# geiger.net
KiCad netlist of a schematic drawn in EAGLE
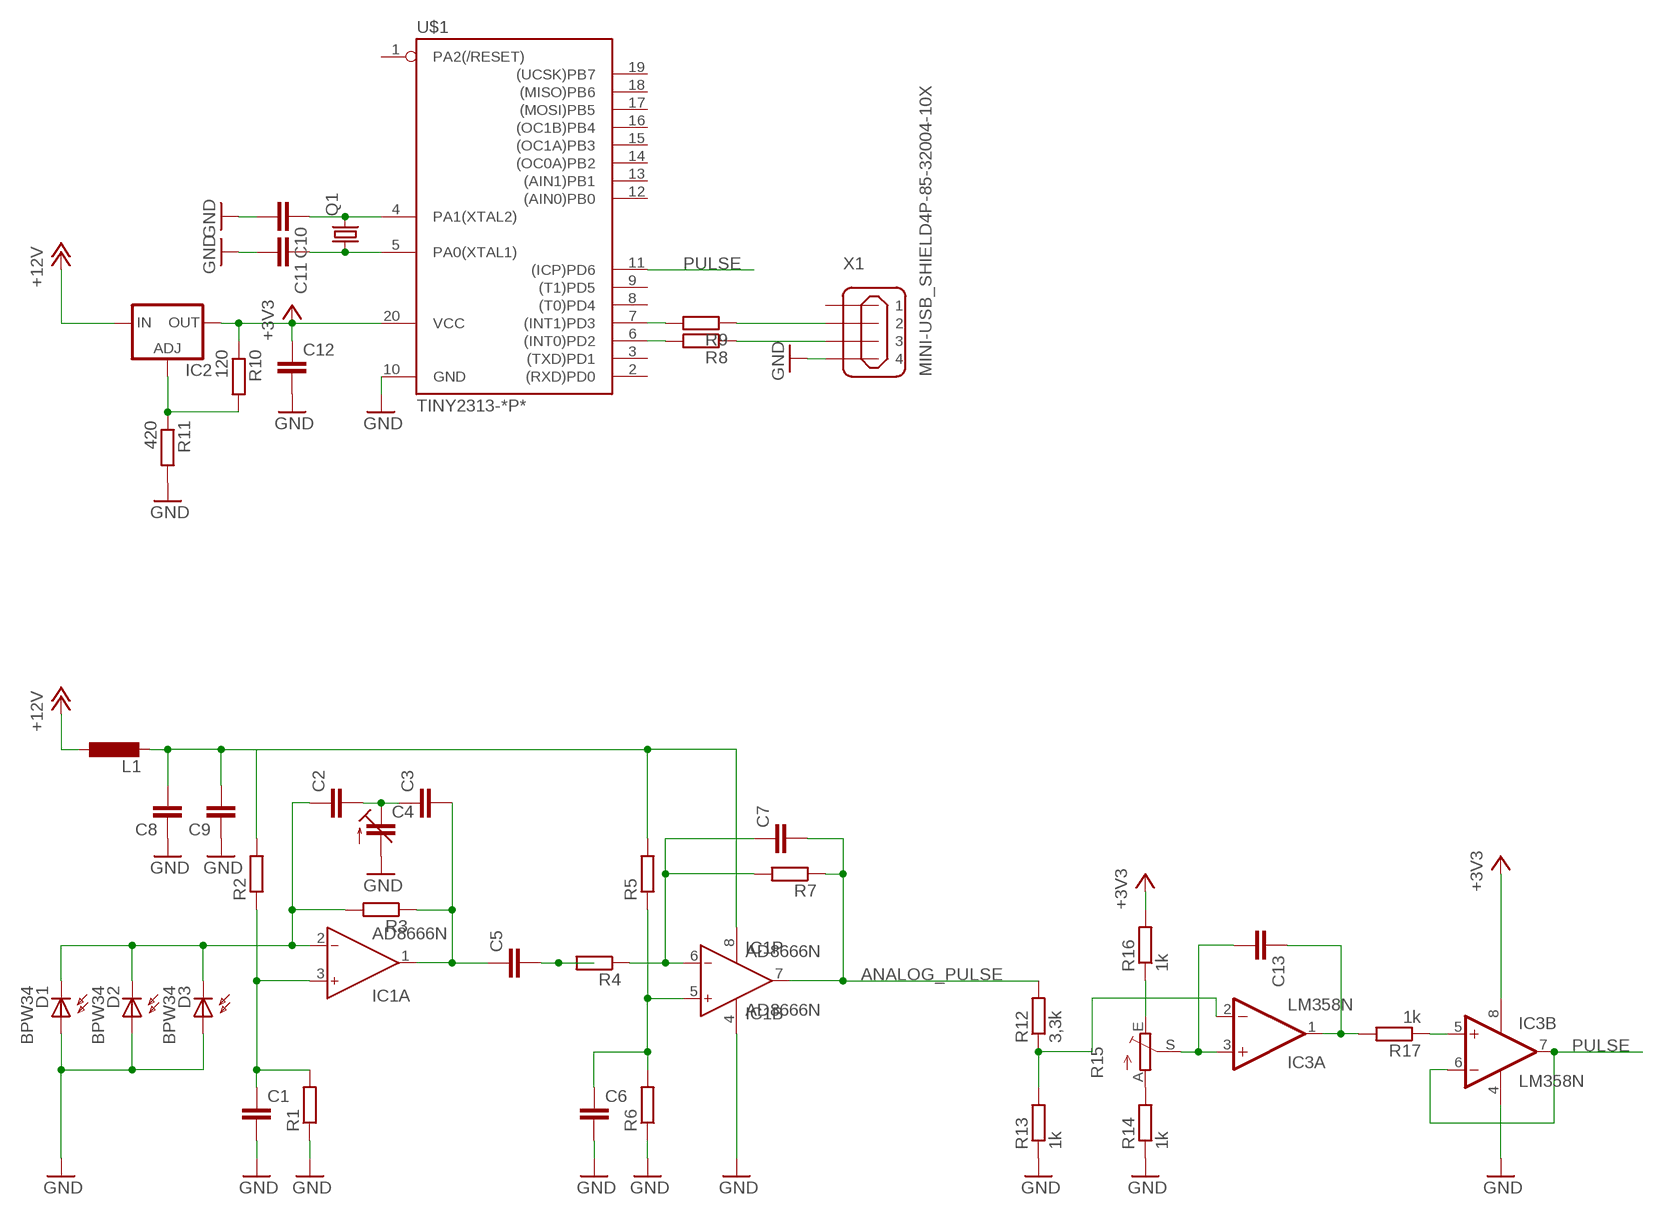
[diagram p0: schematic, sheet 1]

(export (version "E")
  (design (tool "Eeschema 10.0.6"))
  (components
    (comp (ref "C1")
      (value "C-EU025-025X050")
      (footprint "eagle-import:C025-025X050")
      (libsource (lib "eagle-import") (part "C-EU025-025X050"))
    )
    (comp (ref "C2")
      (value "C-EU025-025X050")
      (footprint "eagle-import:C025-025X050")
      (libsource (lib "eagle-import") (part "C-EU025-025X050"))
    )
    (comp (ref "C3")
      (value "C-EU025-025X050")
      (footprint "eagle-import:C025-025X050")
      (libsource (lib "eagle-import") (part "C-EU025-025X050"))
    )
    (comp (ref "C4")
      (value "C-TRIMM3050.504")
      (footprint "eagle-import:CTRIM3050.504")
      (libsource (lib "eagle-import") (part "C-TRIMM3050.504"))
    )
    (comp (ref "C5")
      (value "C-EU025-025X050")
      (footprint "eagle-import:C025-025X050")
      (libsource (lib "eagle-import") (part "C-EU025-025X050"))
    )
    (comp (ref "C6")
      (value "C-EU025-025X050")
      (footprint "eagle-import:C025-025X050")
      (libsource (lib "eagle-import") (part "C-EU025-025X050"))
    )
    (comp (ref "C7")
      (value "C-EU025-025X050")
      (footprint "eagle-import:C025-025X050")
      (libsource (lib "eagle-import") (part "C-EU025-025X050"))
    )
    (comp (ref "C8")
      (value "C-EU025-025X050")
      (footprint "eagle-import:C025-025X050")
      (libsource (lib "eagle-import") (part "C-EU025-025X050"))
    )
    (comp (ref "C9")
      (value "C-EU025-025X050")
      (footprint "eagle-import:C025-025X050")
      (libsource (lib "eagle-import") (part "C-EU025-025X050"))
    )
    (comp (ref "C10")
      (value "C-EU025-025X050")
      (footprint "eagle-import:C025-025X050")
      (libsource (lib "eagle-import") (part "C-EU025-025X050"))
    )
    (comp (ref "C11")
      (value "C-EU025-025X050")
      (footprint "eagle-import:C025-025X050")
      (libsource (lib "eagle-import") (part "C-EU025-025X050"))
    )
    (comp (ref "C12")
      (value "C-EU025-025X050")
      (footprint "eagle-import:C025-025X050")
      (libsource (lib "eagle-import") (part "C-EU025-025X050"))
    )
    (comp (ref "C13")
      (value "C-EU025-025X050")
      (footprint "eagle-import:C025-025X050")
      (libsource (lib "eagle-import") (part "C-EU025-025X050"))
    )
    (comp (ref "D1")
      (value "BPW34")
      (footprint "eagle-import:BPW32")
      (libsource (lib "eagle-import") (part "BPW32"))
    )
    (comp (ref "D2")
      (value "BPW34")
      (footprint "eagle-import:BPW32")
      (libsource (lib "eagle-import") (part "BPW32"))
    )
    (comp (ref "D3")
      (value "BPW34")
      (footprint "eagle-import:BPW32")
      (libsource (lib "eagle-import") (part "BPW32"))
    )
    (comp (ref "IC1")
      (value "AD8666N")
      (footprint "eagle-import:DIL08")
      (libsource (lib "eagle-import") (part "AD8066N"))
    )
    (comp (ref "IC2")
      (value "LM317L")
      (footprint "eagle-import:317L")
      (libsource (lib "eagle-import") (part "LM317L"))
    )
    (comp (ref "IC3")
      (value "LM358N")
      (footprint "eagle-import:DIL08")
      (libsource (lib "eagle-import") (part "LM358N"))
    )
    (comp (ref "L1")
      (value "L-EU2200-12.7")
      (footprint "eagle-import:2200-12.7")
      (libsource (lib "eagle-import") (part "L-EU2200-12.7"))
    )
    (comp (ref "Q1")
      (value "CRYSTALHC49S")
      (footprint "eagle-import:HC49_S")
      (libsource (lib "eagle-import") (part "CRYSTALHC49S"))
    )
    (comp (ref "R1")
      (value "R-EU_0207/7")
      (footprint "eagle-import:0207_7")
      (libsource (lib "eagle-import") (part "R-EU_0207/7"))
    )
    (comp (ref "R2")
      (value "R-EU_0207/7")
      (footprint "eagle-import:0207_7")
      (libsource (lib "eagle-import") (part "R-EU_0207/7"))
    )
    (comp (ref "R3")
      (value "R-EU_0207/7")
      (footprint "eagle-import:0207_7")
      (libsource (lib "eagle-import") (part "R-EU_0207/7"))
    )
    (comp (ref "R4")
      (value "R-EU_0207/7")
      (footprint "eagle-import:0207_7")
      (libsource (lib "eagle-import") (part "R-EU_0207/7"))
    )
    (comp (ref "R5")
      (value "R-EU_0207/7")
      (footprint "eagle-import:0207_7")
      (libsource (lib "eagle-import") (part "R-EU_0207/7"))
    )
    (comp (ref "R6")
      (value "R-EU_0207/7")
      (footprint "eagle-import:0207_7")
      (libsource (lib "eagle-import") (part "R-EU_0207/7"))
    )
    (comp (ref "R7")
      (value "R-EU_0207/7")
      (footprint "eagle-import:0207_7")
      (libsource (lib "eagle-import") (part "R-EU_0207/7"))
    )
    (comp (ref "R8")
      (value "R-EU_0207/7")
      (footprint "eagle-import:0207_7")
      (libsource (lib "eagle-import") (part "R-EU_0207/7"))
    )
    (comp (ref "R9")
      (value "R-EU_0207/7")
      (footprint "eagle-import:0207_7")
      (libsource (lib "eagle-import") (part "R-EU_0207/7"))
    )
    (comp (ref "R10")
      (value "120")
      (footprint "eagle-import:0207_7")
      (libsource (lib "eagle-import") (part "R-EU_0207/7"))
    )
    (comp (ref "R11")
      (value "420")
      (footprint "eagle-import:0207_7")
      (libsource (lib "eagle-import") (part "R-EU_0207/7"))
    )
    (comp (ref "R12")
      (value "3,3k")
      (footprint "eagle-import:0207_7")
      (libsource (lib "eagle-import") (part "R-EU_0207/7"))
    )
    (comp (ref "R13")
      (value "1k")
      (footprint "eagle-import:0207_7")
      (libsource (lib "eagle-import") (part "R-EU_0207/7"))
    )
    (comp (ref "R14")
      (value "1k")
      (footprint "eagle-import:0207_7")
      (libsource (lib "eagle-import") (part "R-EU_0207/7"))
    )
    (comp (ref "R15")
      (value "TRIM_EU-LI10")
      (footprint "eagle-import:LI10")
      (libsource (lib "eagle-import") (part "TRIM_EU-LI10"))
    )
    (comp (ref "R16")
      (value "1k")
      (footprint "eagle-import:0207_7")
      (libsource (lib "eagle-import") (part "R-EU_0207/7"))
    )
    (comp (ref "R17")
      (value "1k")
      (footprint "eagle-import:0207_7")
      (libsource (lib "eagle-import") (part "R-EU_0207/7"))
    )
    (comp (ref "U$1")
      (value "TINY2313-*P*")
      (footprint "eagle-import:DIL20")
      (libsource (lib "eagle-import") (part "TINY2313-P"))
    )
    (comp (ref "X1")
      (value "MINI-USB_SHIELD4P-85-32004-10X")
      (footprint "eagle-import:85-32004-10X")
      (libsource (lib "eagle-import") (part "MINI-USB_SHIELD4P-85-32004-10X"))
    )
  )
  (nets
    (net (code "1") (name "+3V3") (class "Default")
      (node (ref "C12") (pin "1") (pinfunction "1_1") (pintype "passive"))
      (node (ref "IC2") (pin "2") (pinfunction "OUT_2") (pintype "passive"))
      (node (ref "IC3") (pin "8") (pinfunction "V+_8") (pintype "power_in"))
      (node (ref "R10") (pin "1") (pinfunction "1_1") (pintype "passive"))
      (node (ref "R16") (pin "2") (pinfunction "2_2") (pintype "passive"))
      (node (ref "U$1") (pin "20") (pinfunction "VCC_20") (pintype "power_in"))
    )
    (net (code "2") (name "+12V") (class "Default")
      (node (ref "IC2") (pin "3") (pinfunction "IN_3") (pintype "input"))
      (node (ref "L1") (pin "1") (pinfunction "1_1") (pintype "passive"))
    )
    (net (code "3") (name "/ANALOG_PULSE") (class "Default")
      (node (ref "C7") (pin "2") (pinfunction "2_2") (pintype "passive"))
      (node (ref "IC1") (pin "7") (pinfunction "OUT_7") (pintype "output"))
      (node (ref "R12") (pin "2") (pinfunction "2_2") (pintype "passive"))
      (node (ref "R7") (pin "1") (pinfunction "1_1") (pintype "passive"))
    )
    (net (code "4") (name "/PULSE") (class "Default")
      (node (ref "IC3") (pin "6") (pinfunction "-IN_6") (pintype "input"))
      (node (ref "IC3") (pin "7") (pinfunction "OUT_7") (pintype "output"))
      (node (ref "U$1") (pin "11") (pinfunction "(ICP)PD6_11") (pintype "bidirectional"))
    )
    (net (code "5") (name "GND") (class "Default")
      (node (ref "C1") (pin "2") (pinfunction "2_2") (pintype "passive"))
      (node (ref "C10") (pin "2") (pinfunction "2_2") (pintype "passive"))
      (node (ref "C11") (pin "2") (pinfunction "2_2") (pintype "passive"))
      (node (ref "C12") (pin "2") (pinfunction "2_2") (pintype "passive"))
      (node (ref "C4") (pin "2") (pinfunction "A_2") (pintype "passive"))
      (node (ref "C6") (pin "2") (pinfunction "2_2") (pintype "passive"))
      (node (ref "C8") (pin "1") (pinfunction "1_1") (pintype "passive"))
      (node (ref "C9") (pin "1") (pinfunction "1_1") (pintype "passive"))
      (node (ref "D1") (pin "A") (pinfunction "A_A") (pintype "passive"))
      (node (ref "D2") (pin "A") (pinfunction "A_A") (pintype "passive"))
      (node (ref "D3") (pin "A") (pinfunction "A_A") (pintype "passive"))
      (node (ref "IC1") (pin "4") (pinfunction "V-_4") (pintype "power_in"))
      (node (ref "IC3") (pin "4") (pinfunction "V-_4") (pintype "power_in"))
      (node (ref "R1") (pin "1") (pinfunction "1_1") (pintype "passive"))
      (node (ref "R11") (pin "2") (pinfunction "2_2") (pintype "passive"))
      (node (ref "R13") (pin "1") (pinfunction "1_1") (pintype "passive"))
      (node (ref "R14") (pin "1") (pinfunction "1_1") (pintype "passive"))
      (node (ref "R6") (pin "1") (pinfunction "1_1") (pintype "passive"))
      (node (ref "U$1") (pin "10") (pinfunction "GND_10") (pintype "power_in"))
      (node (ref "X1") (pin "4") (pinfunction "4_4") (pintype "passive"))
    )
    (net (code "6") (name "Net-(C4-E)") (class "Default")
      (node (ref "C2") (pin "2") (pinfunction "2_2") (pintype "passive"))
      (node (ref "C3") (pin "1") (pinfunction "1_1") (pintype "passive"))
      (node (ref "C4") (pin "1") (pinfunction "E_1") (pintype "passive"))
    )
    (net (code "7") (name "Net-(C5-Pad2)") (class "Default")
      (node (ref "C5") (pin "2") (pinfunction "2_2") (pintype "passive"))
      (node (ref "R4") (pin "2") (pinfunction "2_2") (pintype "passive"))
    )
    (net (code "8") (name "Net-(D1-C)") (class "Default")
      (node (ref "C2") (pin "1") (pinfunction "1_1") (pintype "passive"))
      (node (ref "D1") (pin "K") (pinfunction "C_K") (pintype "passive"))
      (node (ref "D2") (pin "K") (pinfunction "C_K") (pintype "passive"))
      (node (ref "D3") (pin "K") (pinfunction "C_K") (pintype "passive"))
      (node (ref "IC1") (pin "2") (pinfunction "IN-_2") (pintype "input"))
      (node (ref "R3") (pin "2") (pinfunction "2_2") (pintype "passive"))
    )
    (net (code "9") (name "Net-(IC1A-IN+)") (class "Default")
      (node (ref "C1") (pin "1") (pinfunction "1_1") (pintype "passive"))
      (node (ref "IC1") (pin "3") (pinfunction "IN+_3") (pintype "input"))
      (node (ref "R1") (pin "2") (pinfunction "2_2") (pintype "passive"))
      (node (ref "R2") (pin "1") (pinfunction "1_1") (pintype "passive"))
    )
    (net (code "10") (name "Net-(IC1A-OUT)") (class "Default")
      (node (ref "C3") (pin "2") (pinfunction "2_2") (pintype "passive"))
      (node (ref "C5") (pin "1") (pinfunction "1_1") (pintype "passive"))
      (node (ref "IC1") (pin "1") (pinfunction "OUT_1") (pintype "output"))
      (node (ref "R3") (pin "1") (pinfunction "1_1") (pintype "passive"))
    )
    (net (code "11") (name "Net-(IC1B-IN+)") (class "Default")
      (node (ref "C6") (pin "1") (pinfunction "1_1") (pintype "passive"))
      (node (ref "IC1") (pin "5") (pinfunction "IN+_5") (pintype "input"))
      (node (ref "R5") (pin "1") (pinfunction "1_1") (pintype "passive"))
      (node (ref "R6") (pin "2") (pinfunction "2_2") (pintype "passive"))
    )
    (net (code "12") (name "Net-(IC1B-IN-)") (class "Default")
      (node (ref "C7") (pin "1") (pinfunction "1_1") (pintype "passive"))
      (node (ref "IC1") (pin "6") (pinfunction "IN-_6") (pintype "input"))
      (node (ref "R4") (pin "1") (pinfunction "1_1") (pintype "passive"))
      (node (ref "R7") (pin "2") (pinfunction "2_2") (pintype "passive"))
    )
    (net (code "13") (name "Net-(IC1C-V+)") (class "Default")
      (node (ref "C8") (pin "2") (pinfunction "2_2") (pintype "passive"))
      (node (ref "C9") (pin "2") (pinfunction "2_2") (pintype "passive"))
      (node (ref "IC1") (pin "8") (pinfunction "V+_8") (pintype "power_in"))
      (node (ref "L1") (pin "2") (pinfunction "2_2") (pintype "passive"))
      (node (ref "R2") (pin "2") (pinfunction "2_2") (pintype "passive"))
      (node (ref "R5") (pin "2") (pinfunction "2_2") (pintype "passive"))
    )
    (net (code "14") (name "Net-(IC2-ADJ)") (class "Default")
      (node (ref "IC2") (pin "1") (pinfunction "ADJ_1") (pintype "input"))
      (node (ref "R10") (pin "2") (pinfunction "2_2") (pintype "passive"))
      (node (ref "R11") (pin "1") (pinfunction "1_1") (pintype "passive"))
    )
    (net (code "15") (name "Net-(IC3A-+IN)") (class "Default")
      (node (ref "C13") (pin "2") (pinfunction "2_2") (pintype "passive"))
      (node (ref "IC3") (pin "3") (pinfunction "+IN_3") (pintype "input"))
      (node (ref "R15") (pin "S") (pinfunction "S_S") (pintype "passive"))
    )
    (net (code "16") (name "Net-(IC3A--IN)") (class "Default")
      (node (ref "IC3") (pin "2") (pinfunction "-IN_2") (pintype "input"))
      (node (ref "R12") (pin "1") (pinfunction "1_1") (pintype "passive"))
      (node (ref "R13") (pin "2") (pinfunction "2_2") (pintype "passive"))
    )
    (net (code "17") (name "Net-(IC3A-OUT)") (class "Default")
      (node (ref "C13") (pin "1") (pinfunction "1_1") (pintype "passive"))
      (node (ref "IC3") (pin "1") (pinfunction "OUT_1") (pintype "output"))
      (node (ref "R17") (pin "2") (pinfunction "2_2") (pintype "passive"))
    )
    (net (code "18") (name "Net-(IC3B-+IN)") (class "Default")
      (node (ref "IC3") (pin "5") (pinfunction "+IN_5") (pintype "input"))
      (node (ref "R17") (pin "1") (pinfunction "1_1") (pintype "passive"))
    )
    (net (code "19") (name "Net-(R8-Pad1)") (class "Default")
      (node (ref "R8") (pin "1") (pinfunction "1_1") (pintype "passive"))
      (node (ref "X1") (pin "3") (pinfunction "3_3") (pintype "passive"))
    )
    (net (code "20") (name "Net-(R9-Pad1)") (class "Default")
      (node (ref "R9") (pin "1") (pinfunction "1_1") (pintype "passive"))
      (node (ref "X1") (pin "2") (pinfunction "2_2") (pintype "passive"))
    )
    (net (code "21") (name "Net-(R14-Pad2)") (class "Default")
      (node (ref "R14") (pin "2") (pinfunction "2_2") (pintype "passive"))
      (node (ref "R15") (pin "A") (pinfunction "A_A") (pintype "passive"))
    )
    (net (code "22") (name "Net-(R15-PadE)") (class "Default")
      (node (ref "R15") (pin "E") (pinfunction "E_E") (pintype "passive"))
      (node (ref "R16") (pin "1") (pinfunction "1_1") (pintype "passive"))
    )
    (net (code "23") (name "Net-(U$1-(INT0)PD2)") (class "Default")
      (node (ref "R8") (pin "2") (pinfunction "2_2") (pintype "passive"))
      (node (ref "U$1") (pin "6") (pinfunction "(INT0)PD2_6") (pintype "bidirectional"))
    )
    (net (code "24") (name "Net-(U$1-(INT1)PD3)") (class "Default")
      (node (ref "R9") (pin "2") (pinfunction "2_2") (pintype "passive"))
      (node (ref "U$1") (pin "7") (pinfunction "(INT1)PD3_7") (pintype "bidirectional"))
    )
    (net (code "25") (name "Net-(U$1-PA0(XTAL1))") (class "Default")
      (node (ref "C11") (pin "1") (pinfunction "1_1") (pintype "passive"))
      (node (ref "Q1") (pin "1") (pinfunction "1_1") (pintype "passive"))
      (node (ref "U$1") (pin "5") (pinfunction "PA0(XTAL1)_5") (pintype "bidirectional"))
    )
    (net (code "26") (name "Net-(U$1-PA1(XTAL2))") (class "Default")
      (node (ref "C10") (pin "1") (pinfunction "1_1") (pintype "passive"))
      (node (ref "Q1") (pin "2") (pinfunction "2_2") (pintype "passive"))
      (node (ref "U$1") (pin "4") (pinfunction "PA1(XTAL2)_4") (pintype "bidirectional"))
    )
    (net (code "27") (name "unconnected-(U$1-(AIN0)PB0-Pad12)") (class "Default")
      (node (ref "U$1") (pin "12") (pinfunction "(AIN0)PB0_12") (pintype "bidirectional"))
    )
    (net (code "28") (name "unconnected-(U$1-(AIN1)PB1-Pad13)") (class "Default")
      (node (ref "U$1") (pin "13") (pinfunction "(AIN1)PB1_13") (pintype "bidirectional"))
    )
    (net (code "29") (name "unconnected-(U$1-(MISO)PB6-Pad18)") (class "Default")
      (node (ref "U$1") (pin "18") (pinfunction "(MISO)PB6_18") (pintype "bidirectional"))
    )
    (net (code "30") (name "unconnected-(U$1-(MOSI)PB5-Pad17)") (class "Default")
      (node (ref "U$1") (pin "17") (pinfunction "(MOSI)PB5_17") (pintype "bidirectional"))
    )
    (net (code "31") (name "unconnected-(U$1-(OC0A)PB2-Pad14)") (class "Default")
      (node (ref "U$1") (pin "14") (pinfunction "(OC0A)PB2_14") (pintype "bidirectional"))
    )
    (net (code "32") (name "unconnected-(U$1-(OC1A)PB3-Pad15)") (class "Default")
      (node (ref "U$1") (pin "15") (pinfunction "(OC1A)PB3_15") (pintype "bidirectional"))
    )
    (net (code "33") (name "unconnected-(U$1-(OC1B)PB4-Pad16)") (class "Default")
      (node (ref "U$1") (pin "16") (pinfunction "(OC1B)PB4_16") (pintype "bidirectional"))
    )
    (net (code "34") (name "unconnected-(U$1-(RXD)PD0-Pad2)") (class "Default")
      (node (ref "U$1") (pin "2") (pinfunction "(RXD)PD0_2") (pintype "bidirectional"))
    )
    (net (code "35") (name "unconnected-(U$1-(T0)PD4-Pad8)") (class "Default")
      (node (ref "U$1") (pin "8") (pinfunction "(T0)PD4_8") (pintype "bidirectional"))
    )
    (net (code "36") (name "unconnected-(U$1-(T1)PD5-Pad9)") (class "Default")
      (node (ref "U$1") (pin "9") (pinfunction "(T1)PD5_9") (pintype "bidirectional"))
    )
    (net (code "37") (name "unconnected-(U$1-(TXD)PD1-Pad3)") (class "Default")
      (node (ref "U$1") (pin "3") (pinfunction "(TXD)PD1_3") (pintype "bidirectional"))
    )
    (net (code "38") (name "unconnected-(U$1-(UCSK)PB7-Pad19)") (class "Default")
      (node (ref "U$1") (pin "19") (pinfunction "(UCSK)PB7_19") (pintype "bidirectional"))
    )
    (net (code "39") (name "unconnected-(U$1-PA2({slash}RESET)-Pad1)") (class "Default")
      (node (ref "U$1") (pin "1") (pinfunction "PA2(/RESET)_1") (pintype "input"))
    )
    (net (code "40") (name "unconnected-(X1-Pad1)") (class "Default")
      (node (ref "X1") (pin "1") (pinfunction "1_1") (pintype "passive"))
    )
  )
)
